# LoRa-SX1281.net
KiCad netlist of a schematic drawn in Altium Designer
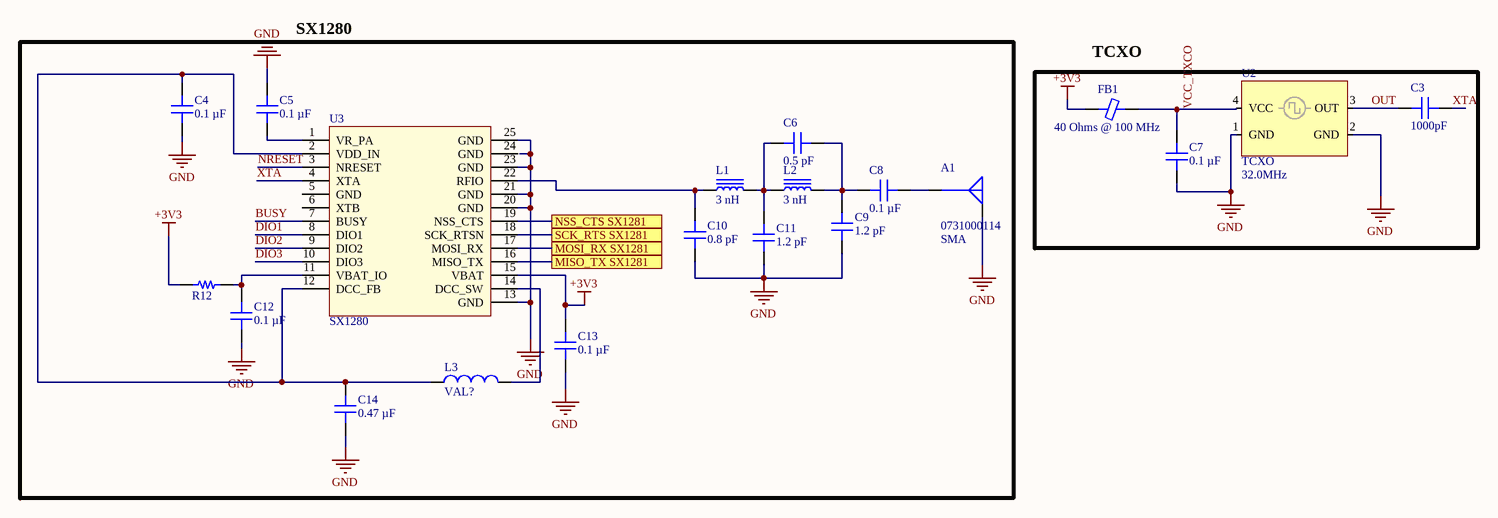
[diagram p0: LoRa-SX1281.SchDoc]

(export (version "E")
  (design (tool "Eeschema 10.0.6"))
  (components
    (comp (ref "A1")
      (value "0731000114")
      (footprint "MOLEX SD-73100-0114")
      (description "CONN SMA RCPT R/A 50 OHM PCB")
      (fields (field (name "CONNECTOR STYLE") "SMA") (field (name "MANUFACTURER") "Molex"))
      (libsource (lib "Celestial Altium Library - altium_library") (part "Basic Antenna"))
    )
    (comp (ref "C3")
      (value "1000pF")
      (footprint "CAP 0402_1005")
      (description "CAP CER 1000PF 50V X7R 0402")
      (fields (field (name "PART NUMBER") "04025C102K4T2A") (field (name "MANUFACTURER") "AVX Corporation"))
      (libsource (lib "Celestial Altium Library - altium_library") (part "Capacitor"))
    )
    (comp (ref "C4")
      (value "0.1 µF")
      (footprint "CAP 0402_1005")
      (description "CAP CER 0.1UF 25V X7R 0402")
      (fields (field (name "PART NUMBER") "CC0402KRX7R8BB104") (field (name "MANUFACTURER") "Yageo"))
      (libsource (lib "Celestial Altium Library - altium_library") (part "Capacitor"))
    )
    (comp (ref "C5")
      (value "0.1 µF")
      (footprint "CAP 0402_1005")
      (description "CAP CER 0.1UF 25V X7R 0402")
      (fields (field (name "PART NUMBER") "CC0402KRX7R8BB104") (field (name "MANUFACTURER") "Yageo"))
      (libsource (lib "") (part "Capacitor_1"))
    )
    (comp (ref "C6")
      (value "0.5 pF")
      (footprint "CAP 0402_1005")
      (description "CAP CER 0.5PF 50V C0G/NP0 0402")
      (fields
        (field (name "PART NUMBER") "GJM1555C1HR50BB01D")
        (field (name "MANUFACTURER") "Murata Electronics")
      )
      (libsource (lib "Celestial Altium Library - altium_library") (part "Capacitor"))
    )
    (comp (ref "C7")
      (value "0.1 µF")
      (footprint "CAP 0402_1005")
      (description "CAP CER 0.1UF 16V X7R 0402")
      (fields
        (field (name "PART NUMBER") "CL05B104KO5NNNC")
        (field (name "MANUFACTURER") "Samsung Electro-Mechanics")
      )
      (libsource (lib "Celestial Altium Library - altium_library") (part "Capacitor"))
    )
    (comp (ref "C8")
      (value "0.1 µF")
      (footprint "CAP 0402_1005")
      (description "CAP CER 0.1UF 16V X7R 0402")
      (fields
        (field (name "PART NUMBER") "CL05B104KO5NNNC")
        (field (name "MANUFACTURER") "Samsung Electro-Mechanics")
      )
      (libsource (lib "Celestial Altium Library - altium_library") (part "Capacitor"))
    )
    (comp (ref "C9")
      (value "1.2 pF")
      (footprint "CAP 0402_1005")
      (description "CAP CER 1.2PF 50V C0G/NPO 0402")
      (fields (field (name "PART NUMBER") "CC0402BRNPO9BN1R2") (field (name "MANUFACTURER") "Yageo"))
      (libsource (lib "Celestial Altium Library - altium_library") (part "Capacitor"))
    )
    (comp (ref "C10")
      (value "0.8 pF")
      (footprint "CAP 0402_1005")
      (description "CAP CER 0.8PF 50V C0G/NPO 0402")
      (fields (field (name "PART NUMBER") "CC0402BRNPO9BNR80") (field (name "MANUFACTURER") "Yageo"))
      (libsource (lib "Celestial Altium Library - altium_library") (part "Capacitor"))
    )
    (comp (ref "C11")
      (value "1.2 pF")
      (footprint "CAP 0402_1005")
      (description "CAP CER 1.2PF 50V C0G/NPO 0402")
      (fields (field (name "PART NUMBER") "CC0402BRNPO9BN1R2") (field (name "MANUFACTURER") "Yageo"))
      (libsource (lib "Celestial Altium Library - altium_library") (part "Capacitor"))
    )
    (comp (ref "C12")
      (value "0.1 µF")
      (footprint "CAP 0402_1005")
      (description "CAP CER 0.1UF 16V X7R 0402")
      (fields
        (field (name "PART NUMBER") "CL05B104KO5NNNC")
        (field (name "MANUFACTURER") "Samsung Electro-Mechanics")
      )
      (libsource (lib "Celestial Altium Library - altium_library") (part "Capacitor"))
    )
    (comp (ref "C13")
      (value "0.1 µF")
      (footprint "CAP 0402_1005")
      (description "CAP CER 0.1UF 16V X7R 0402")
      (fields
        (field (name "PART NUMBER") "CL05B104KO5NNNC")
        (field (name "MANUFACTURER") "Samsung Electro-Mechanics")
      )
      (libsource (lib "Celestial Altium Library - altium_library") (part "Capacitor"))
    )
    (comp (ref "C14")
      (value "0.47 µF")
      (footprint "CAP 0402_1005")
      (description "CAP CER 0.47UF 10V X5R 0402")
      (fields
        (field (name "PART NUMBER") "CL05A474KP5NNNC")
        (field (name "MANUFACTURER") "Samsung Electro-Mechanics")
      )
      (libsource (lib "Celestial Altium Library - altium_library") (part "Capacitor"))
    )
    (comp (ref "FB1")
      (value "40 Ohms @ 100 MHz")
      (footprint "FER 0402_1005")
      (description "FERRITE BEAD 40 OHM 0402 1LN")
      (fields (field (name "PART NUMBER") "MMZ1005Y400CT000") (field (name "MANUFACTURER") "TDK Corporation"))
      (libsource (lib "Celestial Altium Library - altium_library") (part "Ferrite Chip"))
    )
    (comp (ref "L1")
      (value "3 nH")
      (footprint "IND 0402_1005")
      (description "FIXED IND 3NH 1.35A 63 MOHM SMD")
      (fields
        (field (name "PART NUMBER") "LQW15AN3N0B80D")
        (field (name "MANUFACTURER") "Murata Electronics")
      )
      (libsource (lib "Celestial Altium Library - altium_library") (part "Inductor"))
    )
    (comp (ref "L2")
      (value "3 nH")
      (footprint "IND 0402_1005")
      (description "FIXED IND 3NH 1.35A 63 MOHM SMD")
      (fields
        (field (name "PART NUMBER") "LQW15AN3N0B80D")
        (field (name "MANUFACTURER") "Murata Electronics")
      )
      (libsource (lib "Celestial Altium Library - altium_library") (part "Inductor"))
    )
    (comp (ref "L3")
      (value "VAL?")
      (footprint "rlc_805_smd")
      (description "Inductor SMD")
      (fields (field (name "Comment") "Inductor") (field (name "PUBLISHER") "Altium Limited"))
      (libsource (lib "Flight_controller v1.0") (part "Inductor_1"))
    )
    (comp (ref "R12")
      (value "~")
      (footprint "RES 0402_1005")
      (description "RES SMD 0 OHM JUMPER 1/16W 0402")
      (fields (field (name "PART NUMBER") "CRCW04020000Z0ED") (field (name "MANUFACTURER") "Vishay Dale"))
      (libsource (lib "Celestial Altium Library - altium_library") (part "Resistor"))
    )
    (comp (ref "U2")
      (value "TCXO")
      (footprint "TCXO 2.0x1.6mm")
      (fields (field (name "ALTIUM_VALUE") "32.0MHz"))
      (libsource (lib "Flight_controller v1.0") (part "TCXO"))
    )
    (comp (ref "U3")
      (value "SX1280")
      (footprint "vqfn24_4x4mm")
      (description "SX1280 - Ultra low power RF transceiver")
      (libsource (lib "Flight_controller v1.0") (part "SX1280"))
    )
  )
  (nets
    (net (code "1") (name "+3V3") (class "Default")
      (node (ref "C13") (pin "2") (pinfunction "2_2") (pintype "passive"))
      (node (ref "FB1") (pin "1") (pinfunction "1_1") (pintype "passive"))
      (node (ref "R12") (pin "1") (pinfunction "1_1") (pintype "passive"))
      (node (ref "U3") (pin "15") (pinfunction "VBAT_15") (pintype "passive"))
    )
    (net (code "2") (name "/BUSY") (class "Default")
      (node (ref "U3") (pin "7") (pinfunction "BUSY_7") (pintype "passive"))
    )
    (net (code "3") (name "/DIO1") (class "Default")
      (node (ref "U3") (pin "8") (pinfunction "DIO1_8") (pintype "passive"))
    )
    (net (code "4") (name "/DIO2") (class "Default")
      (node (ref "U3") (pin "9") (pinfunction "DIO2_9") (pintype "passive"))
    )
    (net (code "5") (name "/DIO3") (class "Default")
      (node (ref "U3") (pin "10") (pinfunction "DIO3_10") (pintype "passive"))
    )
    (net (code "6") (name "/MISO_TX SX1281") (class "Default")
      (node (ref "U3") (pin "16") (pinfunction "MISO_TX_16") (pintype "passive"))
    )
    (net (code "7") (name "/MOSI_RX SX1281") (class "Default")
      (node (ref "U3") (pin "17") (pinfunction "MOSI_RX_17") (pintype "passive"))
    )
    (net (code "8") (name "/NRESET") (class "Default")
      (node (ref "U3") (pin "3") (pinfunction "NRESET_3") (pintype "passive"))
    )
    (net (code "9") (name "/NSS_CTS SX1281") (class "Default")
      (node (ref "U3") (pin "19") (pinfunction "NSS_CTS_19") (pintype "passive"))
    )
    (net (code "10") (name "/OUT") (class "Default")
      (node (ref "C3") (pin "2") (pinfunction "2_2") (pintype "passive"))
      (node (ref "U2") (pin "3") (pinfunction "OUT_3") (pintype "passive"))
    )
    (net (code "11") (name "/SCK_RTS SX1281") (class "Default")
      (node (ref "U3") (pin "18") (pinfunction "SCK_RTSN_18") (pintype "passive"))
    )
    (net (code "12") (name "/VCC_TXCO") (class "Default")
      (node (ref "C7") (pin "2") (pinfunction "2_2") (pintype "passive"))
      (node (ref "FB1") (pin "2") (pinfunction "2_2") (pintype "passive"))
      (node (ref "U2") (pin "4") (pinfunction "VCC_4") (pintype "passive"))
    )
    (net (code "13") (name "/XTA") (class "Default")
      (node (ref "C3") (pin "1") (pinfunction "1_1") (pintype "passive"))
      (node (ref "U3") (pin "4") (pinfunction "XTA_4") (pintype "passive"))
    )
    (net (code "14") (name "GND") (class "Default")
      (node (ref "A1") (pin "G") (pinfunction "G_G") (pintype "passive"))
      (node (ref "C10") (pin "1") (pinfunction "1_1") (pintype "passive"))
      (node (ref "C11") (pin "1") (pinfunction "1_1") (pintype "passive"))
      (node (ref "C12") (pin "1") (pinfunction "1_1") (pintype "passive"))
      (node (ref "C13") (pin "1") (pinfunction "1_1") (pintype "passive"))
      (node (ref "C14") (pin "1") (pinfunction "1_1") (pintype "passive"))
      (node (ref "C4") (pin "1") (pinfunction "1_1") (pintype "passive"))
      (node (ref "C5") (pin "1") (pinfunction "1_1") (pintype "passive"))
      (node (ref "C7") (pin "1") (pinfunction "1_1") (pintype "passive"))
      (node (ref "C9") (pin "1") (pinfunction "1_1") (pintype "passive"))
      (node (ref "U2") (pin "1") (pinfunction "GND_1") (pintype "passive"))
      (node (ref "U2") (pin "2") (pinfunction "GND_2") (pintype "passive"))
      (node (ref "U3") (pin "13") (pinfunction "GND_13") (pintype "passive"))
      (node (ref "U3") (pin "20") (pinfunction "GND_20") (pintype "passive"))
      (node (ref "U3") (pin "21") (pinfunction "GND_21") (pintype "passive"))
      (node (ref "U3") (pin "23") (pinfunction "GND_23") (pintype "passive"))
      (node (ref "U3") (pin "25") (pinfunction "GND_25") (pintype "passive"))
    )
    (net (code "15") (name "Net-(A1-PadS)") (class "Default")
      (node (ref "A1") (pin "S") (pinfunction "S_S") (pintype "passive"))
      (node (ref "C8") (pin "1") (pinfunction "1_1") (pintype "passive"))
    )
    (net (code "16") (name "Net-(C6-Pad2)") (class "Default")
      (node (ref "C6") (pin "2") (pinfunction "2_2") (pintype "passive"))
      (node (ref "C8") (pin "2") (pinfunction "2_2") (pintype "passive"))
      (node (ref "C9") (pin "2") (pinfunction "2_2") (pintype "passive"))
      (node (ref "L2") (pin "2") (pinfunction "2_2") (pintype "passive"))
    )
    (net (code "17") (name "Net-(C11-Pad2)") (class "Default")
      (node (ref "C11") (pin "2") (pinfunction "2_2") (pintype "passive"))
      (node (ref "C6") (pin "1") (pinfunction "1_1") (pintype "passive"))
      (node (ref "L1") (pin "2") (pinfunction "2_2") (pintype "passive"))
      (node (ref "L2") (pin "1") (pinfunction "1_1") (pintype "passive"))
    )
    (net (code "18") (name "Net-(U3-DCC_FB)") (class "Default")
      (node (ref "C14") (pin "2") (pinfunction "2_2") (pintype "passive"))
      (node (ref "C4") (pin "2") (pinfunction "2_2") (pintype "passive"))
      (node (ref "L3") (pin "1") (pinfunction "1_1") (pintype "passive"))
      (node (ref "U3") (pin "12") (pinfunction "DCC_FB_12") (pintype "passive"))
      (node (ref "U3") (pin "2") (pinfunction "VDD_IN_2") (pintype "passive"))
    )
    (net (code "19") (name "Net-(U3-DCC_SW)") (class "Default")
      (node (ref "L3") (pin "2") (pinfunction "2_2") (pintype "passive"))
      (node (ref "U3") (pin "14") (pinfunction "DCC_SW_14") (pintype "passive"))
    )
    (net (code "20") (name "Net-(U3-RFIO)") (class "Default")
      (node (ref "C10") (pin "2") (pinfunction "2_2") (pintype "passive"))
      (node (ref "L1") (pin "1") (pinfunction "1_1") (pintype "passive"))
      (node (ref "U3") (pin "22") (pinfunction "RFIO_22") (pintype "passive"))
    )
    (net (code "21") (name "Net-(U3-VBAT_IO)") (class "Default")
      (node (ref "C12") (pin "2") (pinfunction "2_2") (pintype "passive"))
      (node (ref "R12") (pin "2") (pinfunction "2_2") (pintype "passive"))
      (node (ref "U3") (pin "11") (pinfunction "VBAT_IO_11") (pintype "passive"))
    )
    (net (code "22") (name "Net-(U3-VR_PA)") (class "Default")
      (node (ref "C5") (pin "2") (pinfunction "2_2") (pintype "passive"))
      (node (ref "U3") (pin "1") (pinfunction "VR_PA_1") (pintype "passive"))
    )
    (net (code "23") (name "unconnected-(U3-GND-Pad5)") (class "Default")
      (node (ref "U3") (pin "5") (pinfunction "GND_5") (pintype "passive"))
    )
    (net (code "24") (name "unconnected-(U3-GND-Pad24)") (class "Default")
      (node (ref "U3") (pin "24") (pinfunction "GND_24") (pintype "passive"))
    )
    (net (code "25") (name "unconnected-(U3-XTB-Pad6)") (class "Default")
      (node (ref "U3") (pin "6") (pinfunction "XTB_6") (pintype "passive"))
    )
  )
)
